# armalampMINI.net
KiCad netlist of a schematic drawn in EAGLE
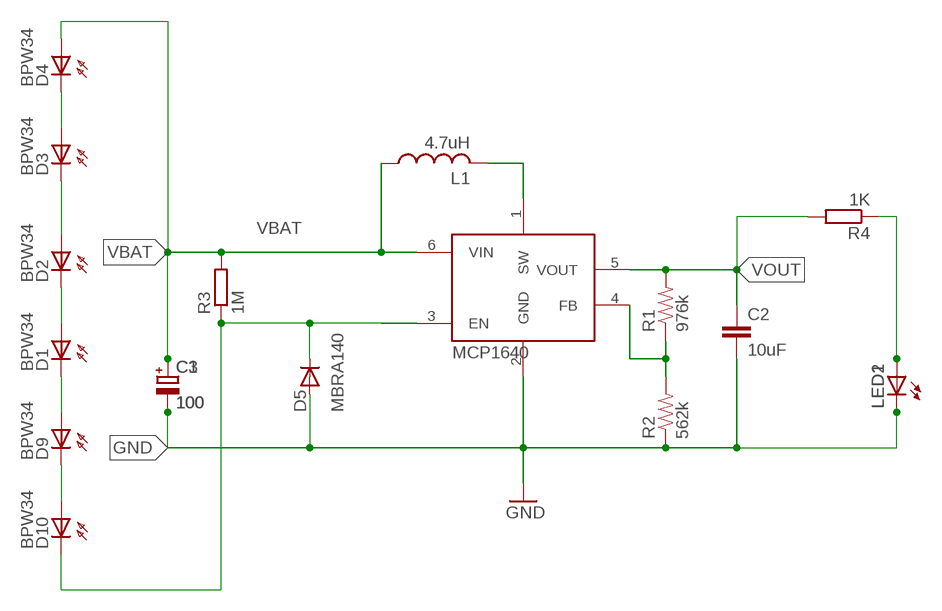
[diagram p0: schematic, sheet 1]

(export (version "E")
  (design (tool "Eeschema 10.0.6"))
  (components
    (comp (ref "C1")
      (value "100")
      (footprint "eagle-import:TT2D7L")
      (libsource (lib "eagle-import") (part "CPOL-EUTT2D7L"))
    )
    (comp (ref "C2")
      (value "10uF")
      (footprint "eagle-import:0805")
      (libsource (lib "eagle-import") (part "CAP0805"))
    )
    (comp (ref "C3")
      (value "100")
      (footprint "eagle-import:TT2D7L")
      (libsource (lib "eagle-import") (part "CPOL-EUTT2D7L"))
    )
    (comp (ref "D1")
      (value "BPW34")
      (footprint "eagle-import:BP104")
      (libsource (lib "eagle-import") (part "BP104"))
    )
    (comp (ref "D2")
      (value "BPW34")
      (footprint "eagle-import:BP104")
      (libsource (lib "eagle-import") (part "BP104"))
    )
    (comp (ref "D3")
      (value "BPW34")
      (footprint "eagle-import:BP104")
      (libsource (lib "eagle-import") (part "BP104"))
    )
    (comp (ref "D4")
      (value "BPW34")
      (footprint "eagle-import:BP104")
      (libsource (lib "eagle-import") (part "BP104"))
    )
    (comp (ref "D5")
      (value "MBRA140")
      (footprint "eagle-import:SOD-323")
      (libsource (lib "eagle-import") (part "DIODESOD"))
    )
    (comp (ref "D9")
      (value "BPW34")
      (footprint "eagle-import:BP104")
      (libsource (lib "eagle-import") (part "BP104"))
    )
    (comp (ref "D10")
      (value "BPW34")
      (footprint "eagle-import:BP104")
      (libsource (lib "eagle-import") (part "BP104"))
    )
    (comp (ref "L1")
      (value "4.7uH")
      (footprint "eagle-import:LQH44")
      (libsource (lib "eagle-import") (part "LLQH44P_P0"))
    )
    (comp (ref "LED1")
      (value "LED5MM")
      (footprint "eagle-import:LED5MM")
      (libsource (lib "eagle-import") (part "LED5MM"))
    )
    (comp (ref "LED2")
      (value "LEDKA-3528ASYC")
      (footprint "eagle-import:KA-3528ASYC")
      (libsource (lib "eagle-import") (part "LEDKA-3528ASYC"))
    )
    (comp (ref "R1")
      (value "976k")
      (footprint "eagle-import:0805")
      (libsource (lib "eagle-import") (part "RESISTOR0805-RES"))
    )
    (comp (ref "R2")
      (value "562k")
      (footprint "eagle-import:0805")
      (libsource (lib "eagle-import") (part "RESISTOR0805-RES"))
    )
    (comp (ref "R3")
      (value "1M")
      (footprint "eagle-import:R0603")
      (libsource (lib "eagle-import") (part "R-EU_R0603"))
    )
    (comp (ref "R4")
      (value "1K")
      (footprint "eagle-import:R0603")
      (libsource (lib "eagle-import") (part "R-EU_R0603"))
    )
    (comp (ref "U1")
      (value "MCP1640")
      (footprint "eagle-import:SOT23-6")
      (libsource (lib "eagle-import") (part "MCP1640"))
    )
  )
  (nets
    (net (code "1") (name "GND") (class "Default")
      (node (ref "C1") (pin "-") (pinfunction "-_-") (pintype "passive"))
      (node (ref "C2") (pin "2") (pinfunction "2_2") (pintype "passive"))
      (node (ref "C3") (pin "-") (pinfunction "-_-") (pintype "passive"))
      (node (ref "D5") (pin "2") (pinfunction "A_2") (pintype "passive"))
      (node (ref "LED1") (pin "K") (pinfunction "C_K") (pintype "passive"))
      (node (ref "LED2") (pin "C") (pinfunction "C_C") (pintype "passive"))
      (node (ref "R2") (pin "1") (pinfunction "1_1") (pintype "passive"))
      (node (ref "U1") (pin "2") (pinfunction "GND_2") (pintype "power_in"))
    )
    (net (code "2") (name "Net-(D1-C)") (class "Default")
      (node (ref "D1") (pin "K") (pinfunction "C_K") (pintype "passive"))
      (node (ref "D9") (pin "A") (pinfunction "A_A") (pintype "passive"))
    )
    (net (code "3") (name "Net-(D2-C)") (class "Default")
      (node (ref "D1") (pin "A") (pinfunction "A_A") (pintype "passive"))
      (node (ref "D2") (pin "K") (pinfunction "C_K") (pintype "passive"))
    )
    (net (code "4") (name "Net-(D3-C)") (class "Default")
      (node (ref "D2") (pin "A") (pinfunction "A_A") (pintype "passive"))
      (node (ref "D3") (pin "K") (pinfunction "C_K") (pintype "passive"))
    )
    (net (code "5") (name "Net-(D4-C)") (class "Default")
      (node (ref "D3") (pin "A") (pinfunction "A_A") (pintype "passive"))
      (node (ref "D4") (pin "K") (pinfunction "C_K") (pintype "passive"))
    )
    (net (code "6") (name "Net-(D9-C)") (class "Default")
      (node (ref "D10") (pin "A") (pinfunction "A_A") (pintype "passive"))
      (node (ref "D9") (pin "K") (pinfunction "C_K") (pintype "passive"))
    )
    (net (code "7") (name "Net-(D10-C)") (class "Default")
      (node (ref "D10") (pin "K") (pinfunction "C_K") (pintype "passive"))
      (node (ref "D5") (pin "1") (pinfunction "C_1") (pintype "passive"))
      (node (ref "R3") (pin "1") (pinfunction "1_1") (pintype "passive"))
      (node (ref "U1") (pin "3") (pinfunction "EN_3") (pintype "input"))
    )
    (net (code "8") (name "Net-(L1-2)") (class "Default")
      (node (ref "L1") (pin "P$2") (pinfunction "2_P$2") (pintype "passive"))
      (node (ref "U1") (pin "1") (pinfunction "SW_1") (pintype "output"))
    )
    (net (code "9") (name "Net-(LED1-PadA)") (class "Default")
      (node (ref "LED1") (pin "A") (pinfunction "A_A") (pintype "passive"))
      (node (ref "LED2") (pin "A") (pinfunction "A_A") (pintype "passive"))
      (node (ref "R4") (pin "1") (pinfunction "1_1") (pintype "passive"))
    )
    (net (code "10") (name "Net-(U1-FB)") (class "Default")
      (node (ref "R1") (pin "1") (pinfunction "1_1") (pintype "passive"))
      (node (ref "R2") (pin "2") (pinfunction "2_2") (pintype "passive"))
      (node (ref "U1") (pin "4") (pinfunction "FB_4") (pintype "input"))
    )
    (net (code "11") (name "VBAT") (class "Default")
      (node (ref "C1") (pin "+") (pinfunction "+_+") (pintype "passive"))
      (node (ref "C3") (pin "+") (pinfunction "+_+") (pintype "passive"))
      (node (ref "D4") (pin "A") (pinfunction "A_A") (pintype "passive"))
      (node (ref "L1") (pin "P$1") (pinfunction "1_P$1") (pintype "passive"))
      (node (ref "R3") (pin "2") (pinfunction "2_2") (pintype "passive"))
      (node (ref "U1") (pin "6") (pinfunction "VIN_6") (pintype "input"))
    )
    (net (code "12") (name "VOUT") (class "Default")
      (node (ref "C2") (pin "1") (pinfunction "1_1") (pintype "passive"))
      (node (ref "R1") (pin "2") (pinfunction "2_2") (pintype "passive"))
      (node (ref "R4") (pin "2") (pinfunction "2_2") (pintype "passive"))
      (node (ref "U1") (pin "5") (pinfunction "VOUT_5") (pintype "output"))
    )
  )
)
